# LS1-LS2.net
KiCad netlist of a schematic drawn in Altium Designer
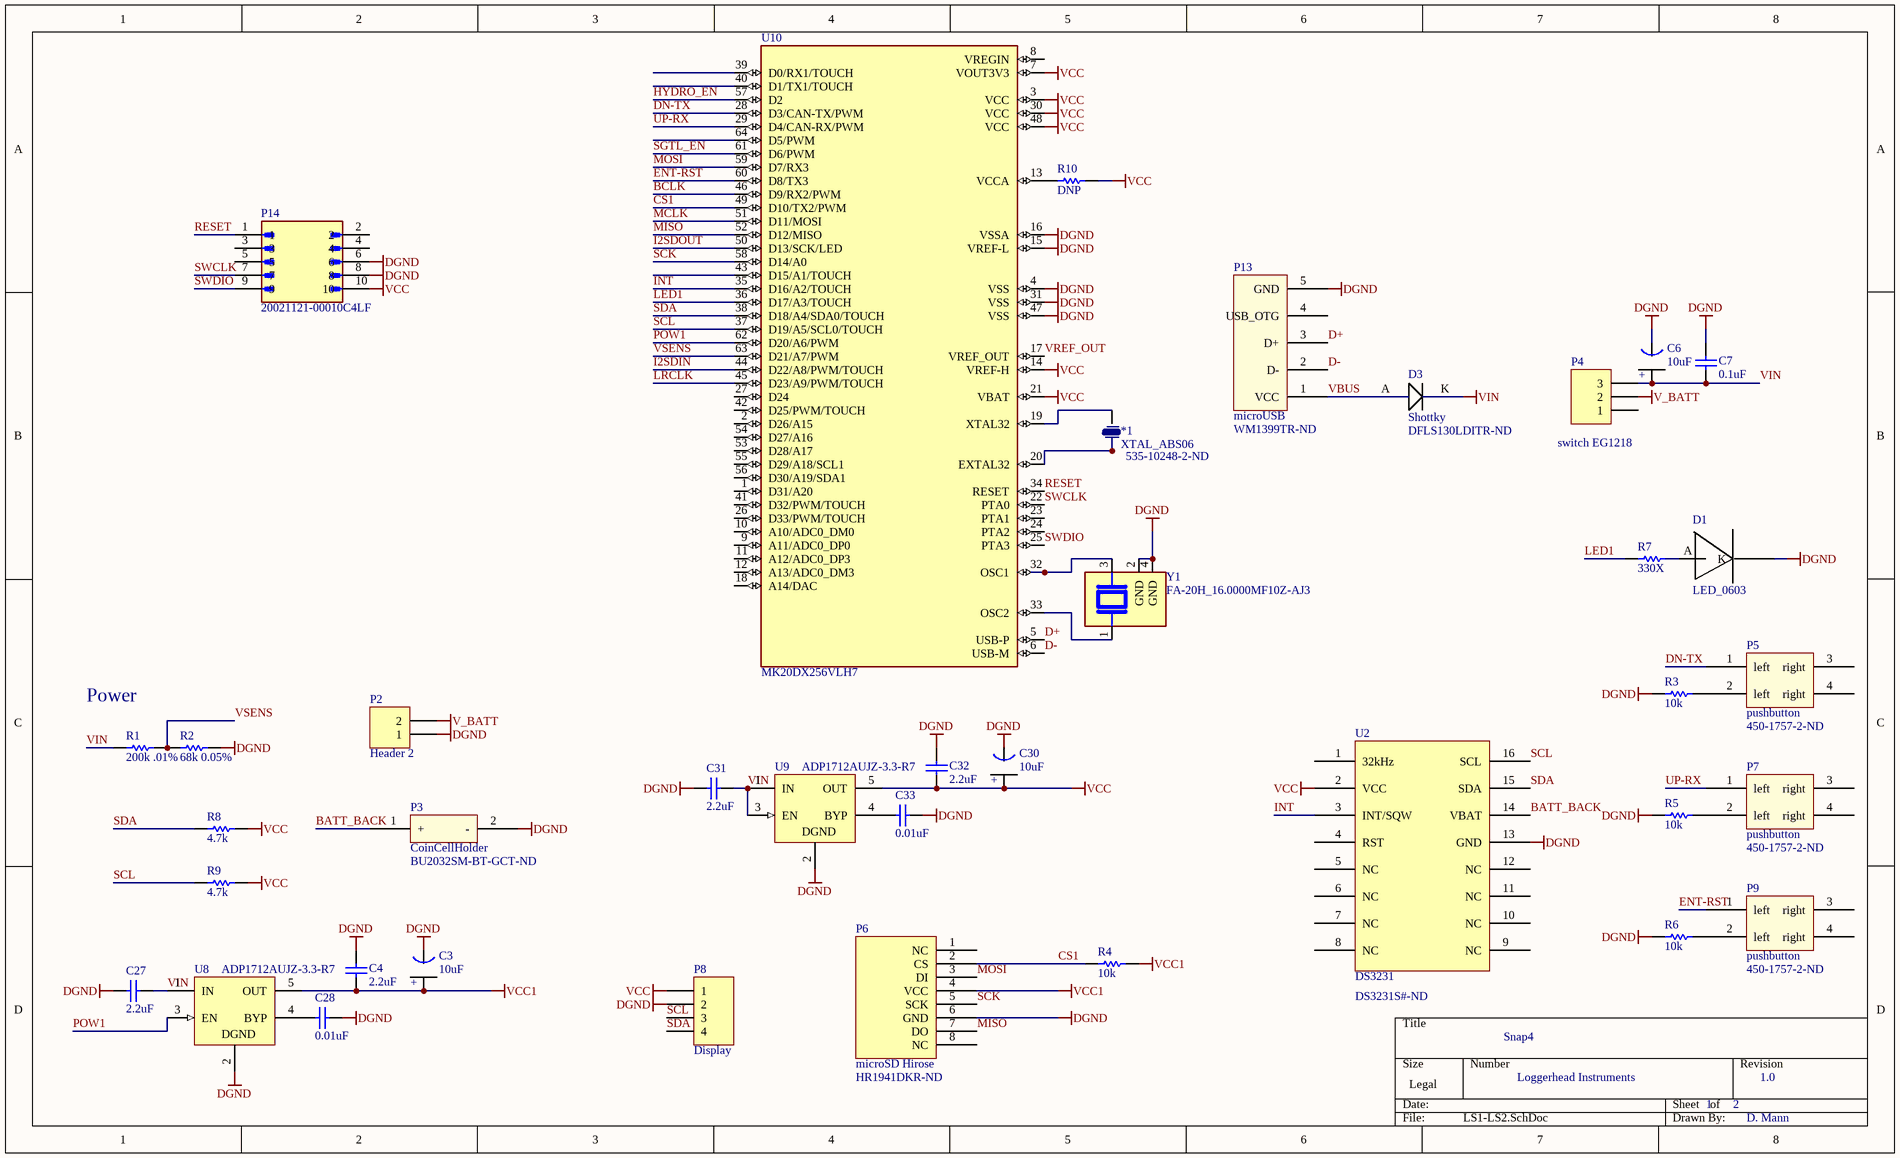
[diagram p0: LS1-LS2.SchDoc]

(export (version "E")
  (design (tool "Eeschema 10.0.6"))
  (components
    (comp (ref "*1")
      (value "XTAL_ABS06")
      (footprint "XTAL-ABS06")
      (fields (field (name "SUPPLIER PART NUMBER 1") "535-10248-2-ND"))
      (libsource (lib "Loggerhead") (part "XTAL_ABS06"))
    )
    (comp (ref "C3") (value "10uF") (footprint "Tant0805") (libsource (lib "Loggerhead") (part "Tant0805")))
    (comp (ref "C4")
      (value "2.2uF")
      (footprint "0402")
      (description "Ceramic Chip Capacitor - Standard")
      (fields (field (name "PUBLISHER") "Altium Limited"))
      (libsource (lib "KEMET Chip Capacitor") (part "C0402"))
    )
    (comp (ref "C6") (value "10uF") (footprint "Tant0805") (libsource (lib "Loggerhead") (part "Tant0805")))
    (comp (ref "C7")
      (value "0.1uF")
      (footprint "0402")
      (description "Ceramic Chip Capacitor - Standard")
      (fields (field (name "PUBLISHER") "Altium Limited"))
      (libsource (lib "KEMET Chip Capacitor") (part "C0402"))
    )
    (comp (ref "C27")
      (value "2.2uF")
      (footprint "0402")
      (description "Ceramic Chip Capacitor - Standard")
      (fields (field (name "PUBLISHER") "Altium Limited"))
      (libsource (lib "KEMET Chip Capacitor") (part "C0402"))
    )
    (comp (ref "C28")
      (value "0.01uF")
      (footprint "0402")
      (description "Ceramic Chip Capacitor - Standard")
      (fields (field (name "PUBLISHER") "Altium Limited"))
      (libsource (lib "KEMET Chip Capacitor") (part "C0402"))
    )
    (comp (ref "C30") (value "10uF") (footprint "Tant0805") (libsource (lib "Loggerhead") (part "Tant0805")))
    (comp (ref "C31")
      (value "2.2uF")
      (footprint "0402")
      (description "Ceramic Chip Capacitor - Standard")
      (fields (field (name "PUBLISHER") "Altium Limited"))
      (libsource (lib "KEMET Chip Capacitor") (part "C0402"))
    )
    (comp (ref "C32")
      (value "2.2uF")
      (footprint "0402")
      (description "Ceramic Chip Capacitor - Standard")
      (fields (field (name "PUBLISHER") "Altium Limited"))
      (libsource (lib "KEMET Chip Capacitor") (part "C0402"))
    )
    (comp (ref "C33")
      (value "0.01uF")
      (footprint "0402")
      (description "Ceramic Chip Capacitor - Standard")
      (fields (field (name "PUBLISHER") "Altium Limited"))
      (libsource (lib "KEMET Chip Capacitor") (part "C0402"))
    )
    (comp (ref "D1")
      (value "LED_0603")
      (footprint "Diode0603")
      (libsource (lib "Loggerhead") (part "LED_0603"))
    )
    (comp (ref "D3")
      (value "Shottky")
      (footprint "DFLS130")
      (fields (field (name "SUPPLIER PART NUMBER 1") "DFLS130LDITR-ND"))
      (libsource (lib "Loggerhead") (part "DFLS130"))
    )
    (comp (ref "P2")
      (value "Header 2")
      (footprint "HDR1X2")
      (description "Header, 2-Pin")
      (fields (field (name "PUBLISHER") "Altium Limited"))
      (libsource (lib "Miscellaneous Connectors") (part "Header 2"))
    )
    (comp (ref "P3")
      (value "CoinCellHolder")
      (footprint "CoinCellHolder")
      (fields (field (name "SUPPLIER PART NUMBER 1") "BU2032SM-BT-GCT-ND"))
      (libsource (lib "Loggerhead") (part "CoinCellHolder"))
    )
    (comp (ref "P4")
      (value "switch EG1218")
      (footprint "HDR1X3")
      (description "Header, 3-Pin")
      (fields (field (name "PUBLISHER") "Altium Limited"))
      (libsource (lib "Miscellaneous Connectors") (part "Header 3"))
    )
    (comp (ref "P5")
      (value "pushbutton")
      (footprint "SOP4")
      (fields (field (name "SUPPLIER PART NUMBER 1") "450-1757-2-ND"))
      (libsource (lib "Loggerhead") (part "pushbutton"))
    )
    (comp (ref "P6")
      (value "microSD Hirose")
      (footprint "DM3D microSD")
      (fields (field (name "SUPPLIER PART NUMBER 1") "HR1941DKR-ND"))
      (libsource (lib "Loggerhead") (part "microSD Hirose"))
    )
    (comp (ref "P7")
      (value "pushbutton")
      (footprint "SOP4")
      (fields (field (name "SUPPLIER PART NUMBER 1") "450-1757-2-ND"))
      (libsource (lib "Loggerhead") (part "pushbutton"))
    )
    (comp (ref "P8")
      (value "Display")
      (footprint "HDR1X4")
      (description "Header, 4-Pin")
      (fields (field (name "PUBLISHER") "Altium Limited"))
      (libsource (lib "Miscellaneous Connectors") (part "Header 4"))
    )
    (comp (ref "P9")
      (value "pushbutton")
      (footprint "SOP4")
      (fields (field (name "SUPPLIER PART NUMBER 1") "450-1757-2-ND"))
      (libsource (lib "Loggerhead") (part "pushbutton"))
    )
    (comp (ref "P13")
      (value "microUSB")
      (footprint "microUSB-B")
      (fields (field (name "SUPPLIER PART NUMBER 1") "WM1399TR-ND"))
      (libsource (lib "Loggerhead") (part "microUSB-B"))
    )
    (comp (ref "P14")
      (value "20021121-00010C4LF")
      (footprint "AMPHENOL_20021121-00010C4LF")
      (fields (field (name "MF") "Amphenol ICC"))
      (libsource (lib "cortex_20021121-00010C4LF") (part "20021121-00010C4LF"))
    )
    (comp (ref "R1")
      (value "200k .01%")
      (footprint "3-0603")
      (fields (field (name "PUBLISHER") "Altium Limited"))
      (libsource (lib "Panasonic Resistor") (part "ERJ3RK"))
    )
    (comp (ref "R2")
      (value "68k 0.05%")
      (footprint "3-0603")
      (fields (field (name "PUBLISHER") "Altium Limited"))
      (libsource (lib "Panasonic Resistor") (part "ERJ3RK"))
    )
    (comp (ref "R3")
      (value "10k")
      (footprint "3-0603")
      (fields (field (name "PUBLISHER") "Altium Limited"))
      (libsource (lib "Panasonic Resistor") (part "ERJ3RK"))
    )
    (comp (ref "R4")
      (value "10k")
      (footprint "3-0603")
      (fields (field (name "PUBLISHER") "Altium Limited"))
      (libsource (lib "Panasonic Resistor") (part "ERJ3RK"))
    )
    (comp (ref "R5")
      (value "10k")
      (footprint "3-0603")
      (fields (field (name "PUBLISHER") "Altium Limited"))
      (libsource (lib "Panasonic Resistor") (part "ERJ3RK"))
    )
    (comp (ref "R6")
      (value "10k")
      (footprint "3-0603")
      (fields (field (name "PUBLISHER") "Altium Limited"))
      (libsource (lib "Panasonic Resistor") (part "ERJ3RK"))
    )
    (comp (ref "R7")
      (value "330X")
      (footprint "3-0603")
      (fields (field (name "PUBLISHER") "Altium Limited"))
      (libsource (lib "Panasonic Resistor") (part "ERJ3RK"))
    )
    (comp (ref "R8")
      (value "4.7k")
      (footprint "3-0603")
      (fields (field (name "PUBLISHER") "Altium Limited"))
      (libsource (lib "Panasonic Resistor") (part "ERJ3RK"))
    )
    (comp (ref "R9")
      (value "4.7k")
      (footprint "3-0603")
      (fields (field (name "PUBLISHER") "Altium Limited"))
      (libsource (lib "Panasonic Resistor") (part "ERJ3RK"))
    )
    (comp (ref "R10")
      (value "DNP")
      (footprint "3-0603")
      (fields (field (name "PUBLISHER") "Altium Limited"))
      (libsource (lib "Panasonic Resistor") (part "ERJ3RK"))
    )
    (comp (ref "U2")
      (value "DS3231")
      (footprint "DS3231")
      (fields (field (name "SUPPLIER PART NUMBER 1") "DS3231S#-ND"))
      (libsource (lib "Loggerhead") (part "DS3231"))
    )
    (comp (ref "U8")
      (value "ADP1712AUJZ-3.3-R7")
      (footprint "MF05A_N")
      (description "Micropower, 150mA Low-Noise Ultra Low-Dropout CMOS Voltage Regulator")
      (fields
        (field (name "PARTNUMBER") "LP3985IM5-3.3")
        (field (name "MANUFACTURER") "National Semiconductor")
        (field (name "PUBLISHER") "Altium Limited")
      )
      (libsource (lib "NSC LDO") (part "LP3985IM5-3.3"))
    )
    (comp (ref "U9")
      (value "ADP1712AUJZ-3.3-R7")
      (footprint "MF05A_N")
      (description "Micropower, 150mA Low-Noise Ultra Low-Dropout CMOS Voltage Regulator")
      (fields
        (field (name "PARTNUMBER") "LP3985IM5-3.3")
        (field (name "MANUFACTURER") "National Semiconductor")
        (field (name "PUBLISHER") "Altium Limited")
      )
      (libsource (lib "NSC LDO") (part "LP3985IM5-3.3"))
    )
    (comp (ref "U10")
      (value "MK20DX256VLH7")
      (footprint "QFP50P1200X1200X160-64N")
      (description "ARMÂ®CortexÂ®-M4Kinetis K20å¾®æŽ§åˆ¶å™¨IC 32ä½72MHz 256KBï¼ˆ256K x 8ï¼‰FLASH 64-LQFPï¼ˆ10x10ï¼‰")
      (fields (field (name "MF") "NXP USA"))
      (libsource (lib "MK20DX256VLH7") (part "MK20DX256VLH7"))
    )
    (comp (ref "Y1")
      (value "FA-20H_16.0000MF10Z-AJ3")
      (footprint "XTAL_FA-20H_16.0000MF10Z-AJ3")
      (description "16 MHz ±10ppm Crystal 8pF 80 Ohms 4-SMD, No Lead")
      (fields (field (name "MF") "EPSON") (field (name "MP") "FA-20H 16.0000MF10Z-AJ3"))
      (libsource (lib "FA-20H_16.0000MF10Z-AJ3") (part "FA-20H_16.0000MF10Z-AJ3"))
    )
  )
  (nets
    (net (code "1") (name "/BATT_BACK") (class "Default")
      (node (ref "P3") (pin "1") (pinfunction "+_1") (pintype "passive"))
      (node (ref "U2") (pin "14") (pinfunction "VBAT_14") (pintype "power_in"))
    )
    (net (code "2") (name "/BCLK") (class "Default")
      (node (ref "U10") (pin "46") (pinfunction "D9/RX2/PWM_46") (pintype "bidirectional"))
    )
    (net (code "3") (name "/CS1") (class "Default")
      (node (ref "P6") (pin "2") (pinfunction "CS_2") (pintype "passive"))
      (node (ref "R4") (pin "2") (pinfunction "2_2") (pintype "passive"))
      (node (ref "U10") (pin "49") (pinfunction "D10/TX2/PWM_49") (pintype "bidirectional"))
    )
    (net (code "4") (name "/D+") (class "Default")
      (node (ref "P13") (pin "3") (pinfunction "D+_3") (pintype "passive"))
      (node (ref "U10") (pin "5") (pinfunction "USB-P_5") (pintype "bidirectional"))
    )
    (net (code "5") (name "/D-") (class "Default")
      (node (ref "P13") (pin "2") (pinfunction "D-_2") (pintype "passive"))
      (node (ref "U10") (pin "6") (pinfunction "USB-M_6") (pintype "bidirectional"))
    )
    (net (code "6") (name "/DN-TX") (class "Default")
      (node (ref "P5") (pin "1") (pinfunction "left_1") (pintype "passive"))
      (node (ref "U10") (pin "28") (pinfunction "D3/CAN-TX/PWM_28") (pintype "bidirectional"))
    )
    (net (code "7") (name "/ENT-RST") (class "Default")
      (node (ref "P9") (pin "1") (pinfunction "left_1") (pintype "passive"))
      (node (ref "U10") (pin "60") (pinfunction "D8/TX3_60") (pintype "bidirectional"))
    )
    (net (code "8") (name "/HYDRO_EN") (class "Default")
      (node (ref "U10") (pin "57") (pinfunction "D2_57") (pintype "bidirectional"))
    )
    (net (code "9") (name "/I2SDIN") (class "Default")
      (node (ref "U10") (pin "44") (pinfunction "D22/A8/PWM/TOUCH_44") (pintype "bidirectional"))
    )
    (net (code "10") (name "/I2SDOUT") (class "Default")
      (node (ref "U10") (pin "50") (pinfunction "D13/SCK/LED_50") (pintype "bidirectional"))
    )
    (net (code "11") (name "/INT") (class "Default")
      (node (ref "U10") (pin "35") (pinfunction "D16/A2/TOUCH_35") (pintype "bidirectional"))
      (node (ref "U2") (pin "3") (pinfunction "INT/SQW_3") (pintype "passive"))
    )
    (net (code "12") (name "/LED1") (class "Default")
      (node (ref "R7") (pin "1") (pinfunction "1_1") (pintype "passive"))
      (node (ref "U10") (pin "36") (pinfunction "D17/A3/TOUCH_36") (pintype "bidirectional"))
    )
    (net (code "13") (name "/LRCLK") (class "Default")
      (node (ref "U10") (pin "45") (pinfunction "D23/A9/PWM/TOUCH_45") (pintype "bidirectional"))
    )
    (net (code "14") (name "/MCLK") (class "Default")
      (node (ref "U10") (pin "51") (pinfunction "D11/MOSI_51") (pintype "bidirectional"))
    )
    (net (code "15") (name "/MISO") (class "Default")
      (node (ref "P6") (pin "7") (pinfunction "DO_7") (pintype "passive"))
      (node (ref "U10") (pin "52") (pinfunction "D12/MISO_52") (pintype "bidirectional"))
    )
    (net (code "16") (name "/MOSI") (class "Default")
      (node (ref "P6") (pin "3") (pinfunction "DI_3") (pintype "passive"))
      (node (ref "U10") (pin "59") (pinfunction "D7/RX3_59") (pintype "bidirectional"))
    )
    (net (code "17") (name "/POW1") (class "Default")
      (node (ref "U10") (pin "62") (pinfunction "D20/A6/PWM_62") (pintype "bidirectional"))
      (node (ref "U8") (pin "3") (pinfunction "EN_3") (pintype "input"))
    )
    (net (code "18") (name "/RESET") (class "Default")
      (node (ref "P14") (pin "1") (pinfunction "1_1") (pintype "passive"))
      (node (ref "U10") (pin "34") (pinfunction "RESET_34") (pintype "bidirectional"))
    )
    (net (code "19") (name "/SCK") (class "Default")
      (node (ref "P6") (pin "5") (pinfunction "SCK_5") (pintype "passive"))
      (node (ref "U10") (pin "58") (pinfunction "D14/A0_58") (pintype "bidirectional"))
    )
    (net (code "20") (name "/SCL") (class "Default")
      (node (ref "P8") (pin "3") (pinfunction "3_3") (pintype "passive"))
      (node (ref "R9") (pin "1") (pinfunction "1_1") (pintype "passive"))
      (node (ref "U10") (pin "37") (pinfunction "D19/A5/SCL0/TOUCH_37") (pintype "bidirectional"))
      (node (ref "U2") (pin "16") (pinfunction "SCL_16") (pintype "passive"))
    )
    (net (code "21") (name "/SDA") (class "Default")
      (node (ref "P8") (pin "4") (pinfunction "4_4") (pintype "passive"))
      (node (ref "R8") (pin "1") (pinfunction "1_1") (pintype "passive"))
      (node (ref "U10") (pin "38") (pinfunction "D18/A4/SDA0/TOUCH_38") (pintype "bidirectional"))
      (node (ref "U2") (pin "15") (pinfunction "SDA_15") (pintype "passive"))
    )
    (net (code "22") (name "/SGTL_EN") (class "Default")
      (node (ref "U10") (pin "61") (pinfunction "D6/PWM_61") (pintype "bidirectional"))
    )
    (net (code "23") (name "/SWCLK") (class "Default")
      (node (ref "P14") (pin "7") (pinfunction "7_7") (pintype "passive"))
      (node (ref "U10") (pin "22") (pinfunction "PTA0_22") (pintype "bidirectional"))
    )
    (net (code "24") (name "/SWDIO") (class "Default")
      (node (ref "P14") (pin "9") (pinfunction "9_9") (pintype "passive"))
      (node (ref "U10") (pin "25") (pinfunction "PTA3_25") (pintype "bidirectional"))
    )
    (net (code "25") (name "/UP-RX") (class "Default")
      (node (ref "P7") (pin "1") (pinfunction "left_1") (pintype "passive"))
      (node (ref "U10") (pin "29") (pinfunction "D4/CAN-RX/PWM_29") (pintype "bidirectional"))
    )
    (net (code "26") (name "/VBUS") (class "Default")
      (node (ref "D3") (pin "A") (pintype "passive"))
      (node (ref "P13") (pin "1") (pinfunction "VCC_1") (pintype "passive"))
    )
    (net (code "27") (name "/VREF_OUT") (class "Default")
      (node (ref "U10") (pin "17") (pinfunction "VREF_OUT_17") (pintype "bidirectional"))
    )
    (net (code "28") (name "/VSENS") (class "Default")
      (node (ref "R1") (pin "1") (pinfunction "1_1") (pintype "passive"))
      (node (ref "R2") (pin "2") (pinfunction "2_2") (pintype "passive"))
      (node (ref "U10") (pin "63") (pinfunction "D21/A7/PWM_63") (pintype "bidirectional"))
    )
    (net (code "29") (name "DGND") (class "Default")
      (node (ref "C27") (pin "2") (pinfunction "2_2") (pintype "passive"))
      (node (ref "C28") (pin "2") (pinfunction "2_2") (pintype "passive"))
      (node (ref "C3") (pin "1") (pinfunction "GND_1") (pintype "passive"))
      (node (ref "C30") (pin "1") (pinfunction "GND_1") (pintype "passive"))
      (node (ref "C31") (pin "2") (pinfunction "2_2") (pintype "passive"))
      (node (ref "C32") (pin "2") (pinfunction "2_2") (pintype "passive"))
      (node (ref "C33") (pin "2") (pinfunction "2_2") (pintype "passive"))
      (node (ref "C4") (pin "2") (pinfunction "2_2") (pintype "passive"))
      (node (ref "C6") (pin "1") (pinfunction "GND_1") (pintype "passive"))
      (node (ref "C7") (pin "2") (pinfunction "2_2") (pintype "passive"))
      (node (ref "D1") (pin "K") (pinfunction "K_K") (pintype "passive"))
      (node (ref "P13") (pin "5") (pinfunction "GND_5") (pintype "passive"))
      (node (ref "P14") (pin "6") (pinfunction "6_6") (pintype "passive"))
      (node (ref "P14") (pin "8") (pinfunction "8_8") (pintype "passive"))
      (node (ref "P2") (pin "1") (pinfunction "1_1") (pintype "passive"))
      (node (ref "P3") (pin "2") (pinfunction "-_2") (pintype "passive"))
      (node (ref "P6") (pin "6") (pinfunction "GND_6") (pintype "passive"))
      (node (ref "P8") (pin "2") (pinfunction "2_2") (pintype "passive"))
      (node (ref "R2") (pin "1") (pinfunction "1_1") (pintype "passive"))
      (node (ref "R3") (pin "2") (pinfunction "2_2") (pintype "passive"))
      (node (ref "R5") (pin "2") (pinfunction "2_2") (pintype "passive"))
      (node (ref "R6") (pin "2") (pinfunction "2_2") (pintype "passive"))
      (node (ref "U10") (pin "15") (pinfunction "VREF-L_15") (pintype "bidirectional"))
      (node (ref "U10") (pin "16") (pinfunction "VSSA_16") (pintype "bidirectional"))
      (node (ref "U10") (pin "31") (pinfunction "VSS_31") (pintype "bidirectional"))
      (node (ref "U10") (pin "4") (pinfunction "VSS_4") (pintype "bidirectional"))
      (node (ref "U10") (pin "47") (pinfunction "VSS_47") (pintype "bidirectional"))
      (node (ref "U2") (pin "13") (pinfunction "GND_13") (pintype "passive"))
      (node (ref "U8") (pin "2") (pinfunction "GND_2") (pintype "power_in"))
      (node (ref "U9") (pin "2") (pinfunction "GND_2") (pintype "power_in"))
      (node (ref "Y1") (pin "2") (pinfunction "GND_2") (pintype "power_in"))
      (node (ref "Y1") (pin "4") (pinfunction "GND_4") (pintype "power_in"))
    )
    (net (code "30") (name "Net-(D1-PadA)") (class "Default")
      (node (ref "D1") (pin "A") (pinfunction "A_A") (pintype "passive"))
      (node (ref "R7") (pin "2") (pinfunction "2_2") (pintype "passive"))
    )
    (net (code "31") (name "Net-(P5-left-Pad2)") (class "Default")
      (node (ref "P5") (pin "2") (pinfunction "left_2") (pintype "passive"))
      (node (ref "R3") (pin "1") (pinfunction "1_1") (pintype "passive"))
    )
    (net (code "32") (name "Net-(P7-left-Pad2)") (class "Default")
      (node (ref "P7") (pin "2") (pinfunction "left_2") (pintype "passive"))
      (node (ref "R5") (pin "1") (pinfunction "1_1") (pintype "passive"))
    )
    (net (code "33") (name "Net-(P9-left-Pad2)") (class "Default")
      (node (ref "P9") (pin "2") (pinfunction "left_2") (pintype "passive"))
      (node (ref "R6") (pin "1") (pinfunction "1_1") (pintype "passive"))
    )
    (net (code "34") (name "Net-(U8-BYP)") (class "Default")
      (node (ref "C28") (pin "1") (pinfunction "1_1") (pintype "passive"))
      (node (ref "U8") (pin "4") (pinfunction "BYP_4") (pintype "passive"))
    )
    (net (code "35") (name "Net-(U9-BYP)") (class "Default")
      (node (ref "C33") (pin "1") (pinfunction "1_1") (pintype "passive"))
      (node (ref "U9") (pin "4") (pinfunction "BYP_4") (pintype "passive"))
    )
    (net (code "36") (name "Net-(U10-EXTAL32)") (class "Default")
      (node (ref "*1") (pin "1") (pinfunction "1_1") (pintype "passive"))
      (node (ref "U10") (pin "20") (pinfunction "EXTAL32_20") (pintype "bidirectional"))
    )
    (net (code "37") (name "Net-(U10-OSC1)") (class "Default")
      (node (ref "U10") (pin "32") (pinfunction "OSC1_32") (pintype "bidirectional"))
      (node (ref "Y1") (pin "3") (pinfunction "2_3") (pintype "passive"))
    )
    (net (code "38") (name "Net-(U10-OSC2)") (class "Default")
      (node (ref "U10") (pin "33") (pinfunction "OSC2_33") (pintype "bidirectional"))
      (node (ref "Y1") (pin "1") (pinfunction "1_1") (pintype "passive"))
    )
    (net (code "39") (name "Net-(U10-VCCA)") (class "Default")
      (node (ref "R10") (pin "1") (pinfunction "1_1") (pintype "passive"))
      (node (ref "U10") (pin "13") (pinfunction "VCCA_13") (pintype "bidirectional"))
    )
    (net (code "40") (name "Net-(U10-XTAL32)") (class "Default")
      (node (ref "*1") (pin "2") (pinfunction "2_2") (pintype "passive"))
      (node (ref "U10") (pin "19") (pinfunction "XTAL32_19") (pintype "bidirectional"))
    )
    (net (code "41") (name "VCC") (class "Default")
      (node (ref "C30") (pin "2") (pinfunction "+_2") (pintype "passive"))
      (node (ref "C32") (pin "1") (pinfunction "1_1") (pintype "passive"))
      (node (ref "P14") (pin "10") (pinfunction "10_10") (pintype "passive"))
      (node (ref "P8") (pin "1") (pinfunction "1_1") (pintype "passive"))
      (node (ref "R10") (pin "2") (pinfunction "2_2") (pintype "passive"))
      (node (ref "R8") (pin "2") (pinfunction "2_2") (pintype "passive"))
      (node (ref "R9") (pin "2") (pinfunction "2_2") (pintype "passive"))
      (node (ref "U10") (pin "14") (pinfunction "VREF-H_14") (pintype "bidirectional"))
      (node (ref "U10") (pin "21") (pinfunction "VBAT_21") (pintype "bidirectional"))
      (node (ref "U10") (pin "3") (pinfunction "VCC_3") (pintype "bidirectional"))
      (node (ref "U10") (pin "30") (pinfunction "VCC_30") (pintype "bidirectional"))
      (node (ref "U10") (pin "48") (pinfunction "VCC_48") (pintype "bidirectional"))
      (node (ref "U10") (pin "7") (pinfunction "VOUT3V3_7") (pintype "bidirectional"))
      (node (ref "U2") (pin "2") (pinfunction "VCC_2") (pintype "power_in"))
      (node (ref "U9") (pin "5") (pinfunction "OUT_5") (pintype "power_in"))
    )
    (net (code "42") (name "VCC1") (class "Default")
      (node (ref "C3") (pin "2") (pinfunction "+_2") (pintype "passive"))
      (node (ref "C4") (pin "1") (pinfunction "1_1") (pintype "passive"))
      (node (ref "P6") (pin "4") (pinfunction "VCC_4") (pintype "passive"))
      (node (ref "R4") (pin "1") (pinfunction "1_1") (pintype "passive"))
      (node (ref "U8") (pin "5") (pinfunction "OUT_5") (pintype "power_in"))
    )
    (net (code "43") (name "VIN") (class "Default")
      (node (ref "C27") (pin "1") (pinfunction "1_1") (pintype "passive"))
      (node (ref "C31") (pin "1") (pinfunction "1_1") (pintype "passive"))
      (node (ref "C6") (pin "2") (pinfunction "+_2") (pintype "passive"))
      (node (ref "C7") (pin "1") (pinfunction "1_1") (pintype "passive"))
      (node (ref "D3") (pin "K") (pintype "passive"))
      (node (ref "P4") (pin "3") (pinfunction "3_3") (pintype "passive"))
      (node (ref "R1") (pin "2") (pinfunction "2_2") (pintype "passive"))
      (node (ref "U8") (pin "1") (pinfunction "IN_1") (pintype "power_in"))
      (node (ref "U9") (pin "1") (pinfunction "IN_1") (pintype "power_in"))
      (node (ref "U9") (pin "3") (pinfunction "EN_3") (pintype "input"))
    )
    (net (code "44") (name "V_BATT") (class "Default")
      (node (ref "P2") (pin "2") (pinfunction "2_2") (pintype "passive"))
      (node (ref "P4") (pin "2") (pinfunction "2_2") (pintype "passive"))
    )
    (net (code "45") (name "unconnected-(P4-Pad1)") (class "Default")
      (node (ref "P4") (pin "1") (pinfunction "1_1") (pintype "passive"))
    )
    (net (code "46") (name "unconnected-(P5-right-Pad3)") (class "Default")
      (node (ref "P5") (pin "3") (pinfunction "right_3") (pintype "passive"))
    )
    (net (code "47") (name "unconnected-(P5-right-Pad4)") (class "Default")
      (node (ref "P5") (pin "4") (pinfunction "right_4") (pintype "passive"))
    )
    (net (code "48") (name "unconnected-(P6-NC-Pad1)") (class "Default")
      (node (ref "P6") (pin "1") (pinfunction "NC_1") (pintype "passive"))
    )
    (net (code "49") (name "unconnected-(P6-NC-Pad8)") (class "Default")
      (node (ref "P6") (pin "8") (pinfunction "NC_8") (pintype "passive"))
    )
    (net (code "50") (name "unconnected-(P7-right-Pad3)") (class "Default")
      (node (ref "P7") (pin "3") (pinfunction "right_3") (pintype "passive"))
    )
    (net (code "51") (name "unconnected-(P7-right-Pad4)") (class "Default")
      (node (ref "P7") (pin "4") (pinfunction "right_4") (pintype "passive"))
    )
    (net (code "52") (name "unconnected-(P9-right-Pad3)") (class "Default")
      (node (ref "P9") (pin "3") (pinfunction "right_3") (pintype "passive"))
    )
    (net (code "53") (name "unconnected-(P9-right-Pad4)") (class "Default")
      (node (ref "P9") (pin "4") (pinfunction "right_4") (pintype "passive"))
    )
    (net (code "54") (name "unconnected-(P13-USB_OTG-Pad4)") (class "Default")
      (node (ref "P13") (pin "4") (pinfunction "USB_OTG_4") (pintype "passive"))
    )
    (net (code "55") (name "unconnected-(P14-Pad2)") (class "Default")
      (node (ref "P14") (pin "2") (pinfunction "2_2") (pintype "passive"))
    )
    (net (code "56") (name "unconnected-(P14-Pad3)") (class "Default")
      (node (ref "P14") (pin "3") (pinfunction "3_3") (pintype "passive"))
    )
    (net (code "57") (name "unconnected-(P14-Pad4)") (class "Default")
      (node (ref "P14") (pin "4") (pinfunction "4_4") (pintype "passive"))
    )
    (net (code "58") (name "unconnected-(P14-Pad5)") (class "Default")
      (node (ref "P14") (pin "5") (pinfunction "5_5") (pintype "passive"))
    )
    (net (code "59") (name "unconnected-(U2-32kHz-Pad1)") (class "Default")
      (node (ref "U2") (pin "1") (pinfunction "32kHz_1") (pintype "passive"))
    )
    (net (code "60") (name "unconnected-(U2-NC-Pad5)") (class "Default")
      (node (ref "U2") (pin "5") (pinfunction "NC_5") (pintype "passive"))
    )
    (net (code "61") (name "unconnected-(U2-NC-Pad6)") (class "Default")
      (node (ref "U2") (pin "6") (pinfunction "NC_6") (pintype "passive"))
    )
    (net (code "62") (name "unconnected-(U2-NC-Pad7)") (class "Default")
      (node (ref "U2") (pin "7") (pinfunction "NC_7") (pintype "passive"))
    )
    (net (code "63") (name "unconnected-(U2-NC-Pad8)") (class "Default")
      (node (ref "U2") (pin "8") (pinfunction "NC_8") (pintype "passive"))
    )
    (net (code "64") (name "unconnected-(U2-NC-Pad9)") (class "Default")
      (node (ref "U2") (pin "9") (pinfunction "NC_9") (pintype "passive"))
    )
    (net (code "65") (name "unconnected-(U2-NC-Pad10)") (class "Default")
      (node (ref "U2") (pin "10") (pinfunction "NC_10") (pintype "passive"))
    )
    (net (code "66") (name "unconnected-(U2-NC-Pad11)") (class "Default")
      (node (ref "U2") (pin "11") (pinfunction "NC_11") (pintype "passive"))
    )
    (net (code "67") (name "unconnected-(U2-NC-Pad12)") (class "Default")
      (node (ref "U2") (pin "12") (pinfunction "NC_12") (pintype "passive"))
    )
    (net (code "68") (name "unconnected-(U2-RST-Pad4)") (class "Default")
      (node (ref "U2") (pin "4") (pinfunction "RST_4") (pintype "passive"))
    )
    (net (code "69") (name "unconnected-(U10-A10{slash}ADC0_DM0-Pad10)") (class "Default")
      (node (ref "U10") (pin "10") (pinfunction "A10/ADC0_DM0_10") (pintype "bidirectional"))
    )
    (net (code "70") (name "unconnected-(U10-A11{slash}ADC0_DP0-Pad9)") (class "Default")
      (node (ref "U10") (pin "9") (pinfunction "A11/ADC0_DP0_9") (pintype "bidirectional"))
    )
    (net (code "71") (name "unconnected-(U10-A12{slash}ADC0_DP3-Pad11)") (class "Default")
      (node (ref "U10") (pin "11") (pinfunction "A12/ADC0_DP3_11") (pintype "bidirectional"))
    )
    (net (code "72") (name "unconnected-(U10-A13{slash}ADC0_DM3-Pad12)") (class "Default")
      (node (ref "U10") (pin "12") (pinfunction "A13/ADC0_DM3_12") (pintype "bidirectional"))
    )
    (net (code "73") (name "unconnected-(U10-A14{slash}DAC-Pad18)") (class "Default")
      (node (ref "U10") (pin "18") (pinfunction "A14/DAC_18") (pintype "bidirectional"))
    )
    (net (code "74") (name "unconnected-(U10-D0{slash}RX1{slash}TOUCH-Pad39)") (class "Default")
      (node (ref "U10") (pin "39") (pinfunction "D0/RX1/TOUCH_39") (pintype "bidirectional"))
    )
    (net (code "75") (name "unconnected-(U10-D1{slash}TX1{slash}TOUCH-Pad40)") (class "Default")
      (node (ref "U10") (pin "40") (pinfunction "D1/TX1/TOUCH_40") (pintype "bidirectional"))
    )
    (net (code "76") (name "unconnected-(U10-D5{slash}PWM-Pad64)") (class "Default")
      (node (ref "U10") (pin "64") (pinfunction "D5/PWM_64") (pintype "bidirectional"))
    )
    (net (code "77") (name "unconnected-(U10-D15{slash}A1{slash}TOUCH-Pad43)") (class "Default")
      (node (ref "U10") (pin "43") (pinfunction "D15/A1/TOUCH_43") (pintype "bidirectional"))
    )
    (net (code "78") (name "unconnected-(U10-D24-Pad27)") (class "Default")
      (node (ref "U10") (pin "27") (pinfunction "D24_27") (pintype "bidirectional"))
    )
    (net (code "79") (name "unconnected-(U10-D25{slash}PWM{slash}TOUCH-Pad42)") (class "Default")
      (node (ref "U10") (pin "42") (pinfunction "D25/PWM/TOUCH_42") (pintype "bidirectional"))
    )
    (net (code "80") (name "unconnected-(U10-D26{slash}A15-Pad2)") (class "Default")
      (node (ref "U10") (pin "2") (pinfunction "D26/A15_2") (pintype "bidirectional"))
    )
    (net (code "81") (name "unconnected-(U10-D27{slash}A16-Pad54)") (class "Default")
      (node (ref "U10") (pin "54") (pinfunction "D27/A16_54") (pintype "bidirectional"))
    )
    (net (code "82") (name "unconnected-(U10-D28{slash}A17-Pad53)") (class "Default")
      (node (ref "U10") (pin "53") (pinfunction "D28/A17_53") (pintype "bidirectional"))
    )
    (net (code "83") (name "unconnected-(U10-D29{slash}A18{slash}SCL1-Pad55)") (class "Default")
      (node (ref "U10") (pin "55") (pinfunction "D29/A18/SCL1_55") (pintype "bidirectional"))
    )
    (net (code "84") (name "unconnected-(U10-D30{slash}A19{slash}SDA1-Pad56)") (class "Default")
      (node (ref "U10") (pin "56") (pinfunction "D30/A19/SDA1_56") (pintype "bidirectional"))
    )
    (net (code "85") (name "unconnected-(U10-D31{slash}A20-Pad1)") (class "Default")
      (node (ref "U10") (pin "1") (pinfunction "D31/A20_1") (pintype "bidirectional"))
    )
    (net (code "86") (name "unconnected-(U10-D32{slash}PWM{slash}TOUCH-Pad41)") (class "Default")
      (node (ref "U10") (pin "41") (pinfunction "D32/PWM/TOUCH_41") (pintype "bidirectional"))
    )
    (net (code "87") (name "unconnected-(U10-D33{slash}PWM{slash}TOUCH-Pad26)") (class "Default")
      (node (ref "U10") (pin "26") (pinfunction "D33/PWM/TOUCH_26") (pintype "bidirectional"))
    )
    (net (code "88") (name "unconnected-(U10-PTA1-Pad23)") (class "Default")
      (node (ref "U10") (pin "23") (pinfunction "PTA1_23") (pintype "bidirectional"))
    )
    (net (code "89") (name "unconnected-(U10-PTA2-Pad24)") (class "Default")
      (node (ref "U10") (pin "24") (pinfunction "PTA2_24") (pintype "bidirectional"))
    )
    (net (code "90") (name "unconnected-(U10-VREGIN-Pad8)") (class "Default")
      (node (ref "U10") (pin "8") (pinfunction "VREGIN_8") (pintype "bidirectional"))
    )
  )
)
